# ORCA_STLINK_MICRO_DEBUG_8_PIN_UART_TOP.net
KiCad netlist of a schematic drawn in EAGLE
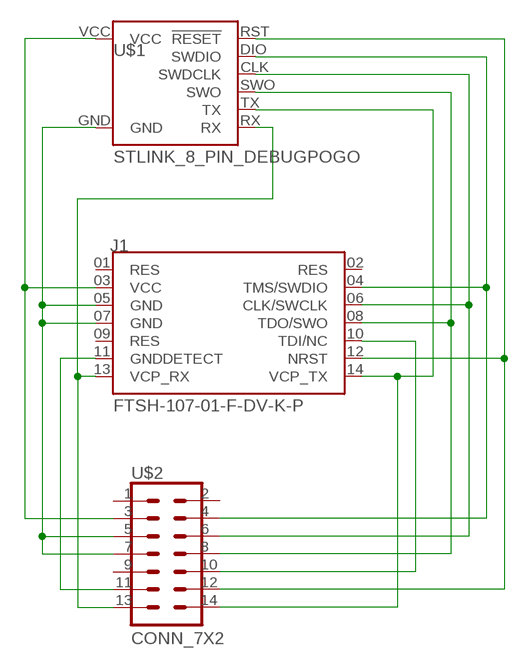
[diagram p0: schematic, sheet 1]

(export (version "E")
  (design (tool "Eeschema 10.0.6"))
  (components
    (comp (ref "J1")
      (value "FTSH-107-01-F-DV-K-P")
      (footprint "eagle-import:SAMTEC_FTSH-107-01-F-DV-K-P")
      (fields (field (name "MANUFACTURER") "Samtec"))
      (libsource (lib "eagle-import") (part "FTSH-107-01-F-DV-K-P"))
    )
    (comp (ref "U$1")
      (value "STLINK_8_PIN_DEBUGPOGO")
      (footprint "eagle-import:STLINK_8_PIN_POGO")
      (libsource (lib "eagle-import") (part "STLINK_8_PIN_DEBUGPOGO"))
    )
    (comp (ref "U$2")
      (value "CONN_7X2")
      (footprint "eagle-import:2X07")
      (libsource (lib "eagle-import") (part "CONN_7X2"))
    )
  )
  (nets
    (net (code "1") (name "Net-(J1-CLK{slash}SWCLK)") (class "Default")
      (node (ref "J1") (pin "06") (pinfunction "CLK/SWCLK_06") (pintype "passive"))
      (node (ref "U$1") (pin "CLK") (pinfunction "SWDCLK_CLK") (pintype "bidirectional"))
      (node (ref "U$2") (pin "6") (pinfunction "P$6_6") (pintype "bidirectional"))
    )
    (net (code "2") (name "Net-(J1-GNDDETECT)") (class "Default")
      (node (ref "J1") (pin "11") (pinfunction "GNDDETECT_11") (pintype "passive"))
      (node (ref "U$2") (pin "11") (pinfunction "P$11_11") (pintype "bidirectional"))
    )
    (net (code "3") (name "Net-(J1-NRST)") (class "Default")
      (node (ref "J1") (pin "12") (pinfunction "NRST_12") (pintype "passive"))
      (node (ref "U$1") (pin "RST") (pinfunction "~{RESET}_RST") (pintype "bidirectional"))
      (node (ref "U$2") (pin "12") (pinfunction "P$12_12") (pintype "bidirectional"))
    )
    (net (code "4") (name "Net-(J1-TDI{slash}NC)") (class "Default")
      (node (ref "J1") (pin "10") (pinfunction "TDI/NC_10") (pintype "passive"))
      (node (ref "U$2") (pin "10") (pinfunction "P$10_10") (pintype "bidirectional"))
    )
    (net (code "5") (name "Net-(J1-TDO{slash}SWO)") (class "Default")
      (node (ref "J1") (pin "08") (pinfunction "TDO/SWO_08") (pintype "passive"))
      (node (ref "U$1") (pin "SWO") (pinfunction "SWO_SWO") (pintype "bidirectional"))
      (node (ref "U$2") (pin "8") (pinfunction "P$8_8") (pintype "bidirectional"))
    )
    (net (code "6") (name "Net-(J1-TMS{slash}SWDIO)") (class "Default")
      (node (ref "J1") (pin "04") (pinfunction "TMS/SWDIO_04") (pintype "passive"))
      (node (ref "U$1") (pin "DIO") (pinfunction "SWDIO_DIO") (pintype "bidirectional"))
      (node (ref "U$2") (pin "4") (pinfunction "P$4_4") (pintype "bidirectional"))
    )
    (net (code "7") (name "Net-(J1-VCC)") (class "Default")
      (node (ref "J1") (pin "03") (pinfunction "VCC_03") (pintype "passive"))
      (node (ref "U$1") (pin "VCC") (pinfunction "VCC_VCC") (pintype "power_in"))
      (node (ref "U$2") (pin "3") (pinfunction "P$3_3") (pintype "bidirectional"))
    )
    (net (code "8") (name "Net-(J1-VCP_RX)") (class "Default")
      (node (ref "J1") (pin "13") (pinfunction "VCP_RX_13") (pintype "passive"))
      (node (ref "U$1") (pin "RX") (pinfunction "RX_RX") (pintype "bidirectional"))
      (node (ref "U$2") (pin "13") (pinfunction "P$13_13") (pintype "bidirectional"))
    )
    (net (code "9") (name "Net-(J1-VCP_TX)") (class "Default")
      (node (ref "J1") (pin "14") (pinfunction "VCP_TX_14") (pintype "passive"))
      (node (ref "U$1") (pin "TX") (pinfunction "TX_TX") (pintype "bidirectional"))
      (node (ref "U$2") (pin "14") (pinfunction "P$14_14") (pintype "bidirectional"))
    )
    (net (code "10") (name "Net-(U$2-P$5)") (class "Default")
      (node (ref "J1") (pin "05") (pinfunction "GND_05") (pintype "passive"))
      (node (ref "J1") (pin "07") (pinfunction "GND_07") (pintype "passive"))
      (node (ref "U$1") (pin "GND") (pinfunction "GND_GND") (pintype "power_in"))
      (node (ref "U$2") (pin "5") (pinfunction "P$5_5") (pintype "bidirectional"))
      (node (ref "U$2") (pin "7") (pinfunction "P$7_7") (pintype "bidirectional"))
    )
    (net (code "11") (name "unconnected-(J1-RES-Pad01)") (class "Default")
      (node (ref "J1") (pin "01") (pinfunction "RES_01") (pintype "no_connect"))
    )
    (net (code "12") (name "unconnected-(J1-RES-Pad02)") (class "Default")
      (node (ref "J1") (pin "02") (pinfunction "RES_02") (pintype "no_connect"))
    )
    (net (code "13") (name "unconnected-(J1-RES-Pad09)") (class "Default")
      (node (ref "J1") (pin "09") (pinfunction "RES_09") (pintype "no_connect"))
    )
    (net (code "14") (name "unconnected-(U$2-P$1-Pad1)") (class "Default")
      (node (ref "U$2") (pin "1") (pinfunction "P$1_1") (pintype "bidirectional"))
    )
    (net (code "15") (name "unconnected-(U$2-P$2-Pad2)") (class "Default")
      (node (ref "U$2") (pin "2") (pinfunction "P$2_2") (pintype "bidirectional"))
    )
    (net (code "16") (name "unconnected-(U$2-P$9-Pad9)") (class "Default")
      (node (ref "U$2") (pin "9") (pinfunction "P$9_9") (pintype "bidirectional"))
    )
  )
)
